# PA_CTRL_TOP.net
KiCad netlist of a schematic drawn in Altium Designer
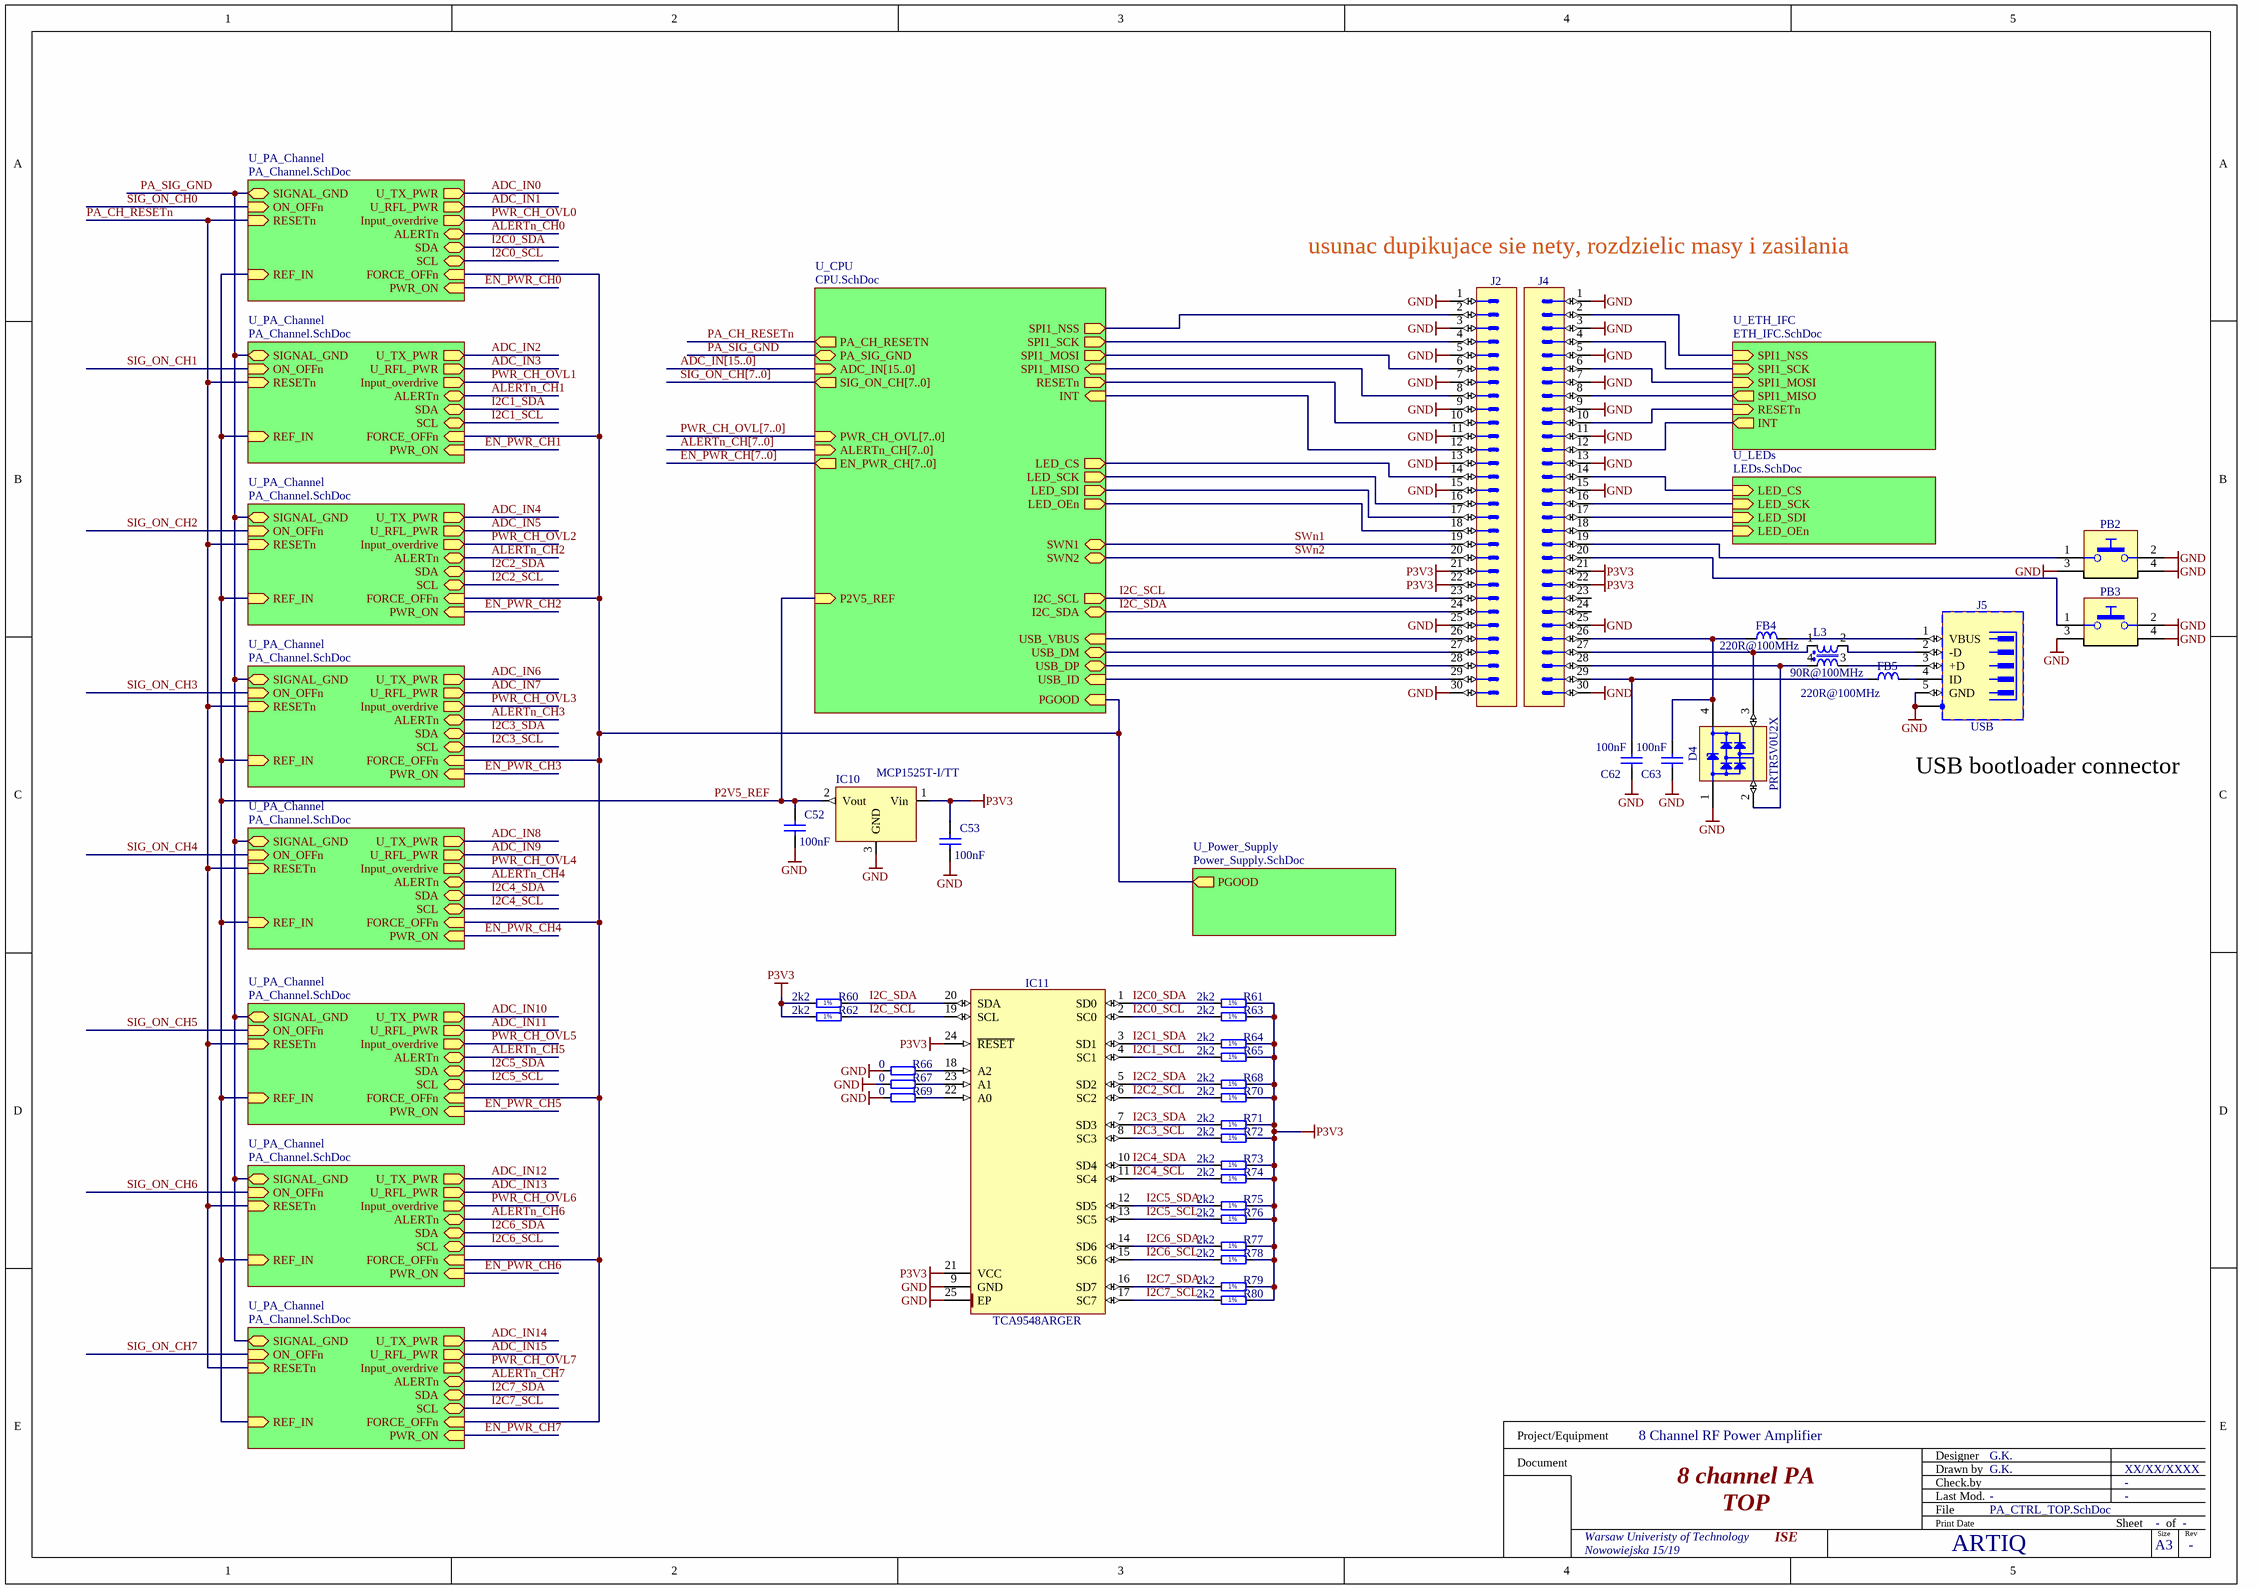
[diagram p0: PA_CTRL_TOP.SchDoc]

(export (version "E")
  (design (tool "Eeschema 10.0.6"))
  (components
    (comp (ref "C52")
      (value "100nF")
      (footprint "CAPC1005X55N")
      (description "Non-polarised capacitor")
      (fields
        (field (name "PART NUMBER") "CC0402_100NF_16V_10%_X7R")
        (field (name "VOLTAGE") "16V")
        (field (name "AUTHOR") "CERN DEM JLC")
      )
      (libsource (lib "Capacitors") (part "Capacitor - non polarized"))
    )
    (comp (ref "C53")
      (value "100nF")
      (footprint "CAPC1005X55N")
      (description "Non-polarised capacitor")
      (fields
        (field (name "PART NUMBER") "CC0402_100NF_16V_10%_X7R")
        (field (name "VOLTAGE") "16V")
        (field (name "AUTHOR") "CERN DEM JLC")
      )
      (libsource (lib "Capacitors") (part "Capacitor - non polarized"))
    )
    (comp (ref "C62")
      (value "100nF")
      (footprint "CAPC0603X33N")
      (description "Non-polarised capacitor")
      (fields
        (field (name "PART NUMBER") "CC0201_100NF_6.3V_10%_X5R")
        (field (name "VOLTAGE") "6.3V")
        (field (name "AUTHOR") "CERN DEM JLC")
      )
      (libsource (lib "Capacitors") (part "Capacitor - non polarized"))
    )
    (comp (ref "C63")
      (value "100nF")
      (footprint "CAPC0603X33N")
      (description "Non-polarised capacitor")
      (fields
        (field (name "PART NUMBER") "CC0201_100NF_6.3V_10%_X5R")
        (field (name "VOLTAGE") "6.3V")
        (field (name "AUTHOR") "CERN DEM JLC")
      )
      (libsource (lib "Capacitors") (part "Capacitor - non polarized"))
    )
    (comp (ref "D4")
      (value "PRTR5V0U2X")
      (footprint "SOT190P230X110-4N")
      (description "Ultra Low Capacitance Double Rail-to-Rail ESD Protection Diode")
      (fields
        (field (name "VOLTAGE") "5.5V")
        (field (name "MANUFACTURER") "NXP SEMICONDUCTORS")
        (field (name "AUTHOR") "CERN DEM JLC")
      )
      (libsource (lib "ICs And Semiconductors") (part "PRTR5V0U2X"))
    )
    (comp (ref "FB4")
      (value "220R@100MHz")
      (footprint "INDC2012X105N")
      (description "Inductor")
      (fields
        (field (name "PART NUMBER") "IND0805_MURATA_BLM21PG221SN1D")
        (field (name "POWER") "2A")
        (field (name "AUTHOR") "CERN DEM JLC")
      )
      (libsource (lib "Inductors & Transformers") (part "Inductor"))
    )
    (comp (ref "FB5")
      (value "220R@100MHz")
      (footprint "INDC2012X105N")
      (description "Inductor")
      (fields
        (field (name "PART NUMBER") "IND0805_MURATA_BLM21PG221SN1D")
        (field (name "POWER") "2A")
        (field (name "AUTHOR") "CERN DEM JLC")
      )
      (libsource (lib "Inductors & Transformers") (part "Inductor"))
    )
    (comp (ref "IC10")
      (value "MCP1525T-I/TT")
      (footprint "SOT95P251X112-3N")
      (description "2.5 voltage reference")
      (libsource (lib "LIBRARY_SCH") (part "REF_MCP1525"))
    )
    (comp (ref "IC11")
      (value "TCA9548ARGER")
      (footprint "QFN50P400X400X100-25N-S220")
      (description "Low Voltage 8-Channel I2C Switch With Reset")
      (fields (field (name "MANUFACTURER") "TEXAS INSTRUMENTS") (field (name "AUTHOR") "CERN DEM JLC"))
      (libsource (lib "ICs And Semiconductors") (part "TCA9548ARGER"))
    )
    (comp (ref "J2")
      (value "~")
      (footprint "3M_N2530-6002RB")
      (description "Connector 30 Male")
      (fields
        (field (name "PART NUMBER") "3M_N2530-6002RB")
        (field (name "MANUFACTURER") "3M")
        (field (name "AUTHOR") "CERN DEM JLC")
      )
      (libsource (lib "Connectors") (part "Connector 30 Male"))
    )
    (comp (ref "J4")
      (value "~")
      (footprint "3M_N2530-6002RB")
      (description "Connector 30 Male")
      (fields
        (field (name "PART NUMBER") "3M_N2530-6002RB")
        (field (name "MANUFACTURER") "3M")
        (field (name "AUTHOR") "CERN DEM JLC")
      )
      (libsource (lib "Connectors") (part "Connector 30 Male"))
    )
    (comp (ref "J5")
      (value "USB")
      (footprint "WURTH_651005136521")
      (description "5 Pin + 1 Shield USB Receptacle")
      (fields
        (field (name "PART NUMBER") "WURTH_651005136521")
        (field (name "MANUFACTURER") "WURTH ELEKTRONIK")
        (field (name "AUTHOR") "CERN DEM JLC")
      )
      (libsource (lib "Connectors") (part "Connector USB 5 Pin + 1Shield"))
    )
    (comp (ref "L3")
      (value "90R@100MHz")
      (footprint "IND_MURATA_DLW21S")
      (description "Inductor Common Mode")
      (fields
        (field (name "PART NUMBER") "IND_MURATA_DLW21SN900SQ2L")
        (field (name "POWER") "330mA")
        (field (name "AUTHOR") "CERN DEM JLC")
      )
      (libsource (lib "Inductors & Transformers") (part "Inductor Common Mode 1Dot-2 4Dot-3"))
    )
    (comp (ref "PB2")
      (value "Push Button")
      (footprint "PB_TYCO_1-1825027-1")
      (description "Push-Button Switch SPDT")
      (fields
        (field (name "PART NUMBER") "PB_TYCO_1-1825027-1")
        (field (name "MANUFACTURER") "TYCO ELECTRONICS")
        (field (name "AUTHOR") "CERN DEM JLC")
      )
      (libsource (lib "Eletro-mechanical") (part "PB SPST 1NO-2NO 34CASE"))
    )
    (comp (ref "PB3")
      (value "Push Button")
      (footprint "PB_TYCO_1-1825027-1")
      (description "Push-Button Switch SPDT")
      (fields
        (field (name "PART NUMBER") "PB_TYCO_1-1825027-1")
        (field (name "MANUFACTURER") "TYCO ELECTRONICS")
        (field (name "AUTHOR") "CERN DEM JLC")
      )
      (libsource (lib "Eletro-mechanical") (part "PB SPST 1NO-2NO 34CASE"))
    )
    (comp (ref "R60")
      (value "2k2")
      (footprint "RESC1005X40N")
      (description "Resistor - 1%")
      (fields
        (field (name "PART NUMBER") "R0402_2K2_1%_0.0625W_100PPM")
        (field (name "POWER") "0.0625W")
        (field (name "AUTHOR") "CERN DEM JLC")
      )
      (libsource (lib "Resistors") (part "Resistor - 1%"))
    )
    (comp (ref "R61")
      (value "2k2")
      (footprint "RESC1005X40N")
      (description "Resistor - 1%")
      (fields
        (field (name "PART NUMBER") "R0402_2K2_1%_0.0625W_100PPM")
        (field (name "POWER") "0.0625W")
        (field (name "AUTHOR") "CERN DEM JLC")
      )
      (libsource (lib "Resistors") (part "Resistor - 1%"))
    )
    (comp (ref "R62")
      (value "2k2")
      (footprint "RESC1005X40N")
      (description "Resistor - 1%")
      (fields
        (field (name "PART NUMBER") "R0402_2K2_1%_0.0625W_100PPM")
        (field (name "POWER") "0.0625W")
        (field (name "AUTHOR") "CERN DEM JLC")
      )
      (libsource (lib "Resistors") (part "Resistor - 1%"))
    )
    (comp (ref "R63")
      (value "2k2")
      (footprint "RESC1005X40N")
      (description "Resistor - 1%")
      (fields
        (field (name "PART NUMBER") "R0402_2K2_1%_0.0625W_100PPM")
        (field (name "POWER") "0.0625W")
        (field (name "AUTHOR") "CERN DEM JLC")
      )
      (libsource (lib "Resistors") (part "Resistor - 1%"))
    )
    (comp (ref "R64")
      (value "2k2")
      (footprint "RESC1005X40N")
      (description "Resistor - 1%")
      (fields
        (field (name "PART NUMBER") "R0402_2K2_1%_0.0625W_100PPM")
        (field (name "POWER") "0.0625W")
        (field (name "AUTHOR") "CERN DEM JLC")
      )
      (libsource (lib "Resistors") (part "Resistor - 1%"))
    )
    (comp (ref "R65")
      (value "2k2")
      (footprint "RESC1005X40N")
      (description "Resistor - 1%")
      (fields
        (field (name "PART NUMBER") "R0402_2K2_1%_0.0625W_100PPM")
        (field (name "POWER") "0.0625W")
        (field (name "AUTHOR") "CERN DEM JLC")
      )
      (libsource (lib "Resistors") (part "Resistor - 1%"))
    )
    (comp (ref "R66")
      (value "0")
      (footprint "RESC1005X40N")
      (description "Resistor")
      (fields
        (field (name "PART NUMBER") "R0402_0R_JUMPER")
        (field (name "MANUFACTURER") "GENERIC")
        (field (name "AUTHOR") "CERN DEM JLC")
      )
      (libsource (lib "Resistors") (part "Resistor"))
    )
    (comp (ref "R67")
      (value "0")
      (footprint "RESC1005X40N")
      (description "Resistor")
      (fields
        (field (name "PART NUMBER") "R0402_0R_JUMPER")
        (field (name "MANUFACTURER") "GENERIC")
        (field (name "AUTHOR") "CERN DEM JLC")
      )
      (libsource (lib "Resistors") (part "Resistor"))
    )
    (comp (ref "R68")
      (value "2k2")
      (footprint "RESC1005X40N")
      (description "Resistor - 1%")
      (fields
        (field (name "PART NUMBER") "R0402_2K2_1%_0.0625W_100PPM")
        (field (name "POWER") "0.0625W")
        (field (name "AUTHOR") "CERN DEM JLC")
      )
      (libsource (lib "Resistors") (part "Resistor - 1%"))
    )
    (comp (ref "R69")
      (value "0")
      (footprint "RESC1005X40N")
      (description "Resistor")
      (fields
        (field (name "PART NUMBER") "R0402_0R_JUMPER")
        (field (name "MANUFACTURER") "GENERIC")
        (field (name "AUTHOR") "CERN DEM JLC")
      )
      (libsource (lib "Resistors") (part "Resistor"))
    )
    (comp (ref "R70")
      (value "2k2")
      (footprint "RESC1005X40N")
      (description "Resistor - 1%")
      (fields
        (field (name "PART NUMBER") "R0402_2K2_1%_0.0625W_100PPM")
        (field (name "POWER") "0.0625W")
        (field (name "AUTHOR") "CERN DEM JLC")
      )
      (libsource (lib "Resistors") (part "Resistor - 1%"))
    )
    (comp (ref "R71")
      (value "2k2")
      (footprint "RESC1005X40N")
      (description "Resistor - 1%")
      (fields
        (field (name "PART NUMBER") "R0402_2K2_1%_0.0625W_100PPM")
        (field (name "POWER") "0.0625W")
        (field (name "AUTHOR") "CERN DEM JLC")
      )
      (libsource (lib "Resistors") (part "Resistor - 1%"))
    )
    (comp (ref "R72")
      (value "2k2")
      (footprint "RESC1005X40N")
      (description "Resistor - 1%")
      (fields
        (field (name "PART NUMBER") "R0402_2K2_1%_0.0625W_100PPM")
        (field (name "POWER") "0.0625W")
        (field (name "AUTHOR") "CERN DEM JLC")
      )
      (libsource (lib "Resistors") (part "Resistor - 1%"))
    )
    (comp (ref "R73")
      (value "2k2")
      (footprint "RESC1005X40N")
      (description "Resistor - 1%")
      (fields
        (field (name "PART NUMBER") "R0402_2K2_1%_0.0625W_100PPM")
        (field (name "POWER") "0.0625W")
        (field (name "AUTHOR") "CERN DEM JLC")
      )
      (libsource (lib "Resistors") (part "Resistor - 1%"))
    )
    (comp (ref "R74")
      (value "2k2")
      (footprint "RESC1005X40N")
      (description "Resistor - 1%")
      (fields
        (field (name "PART NUMBER") "R0402_2K2_1%_0.0625W_100PPM")
        (field (name "POWER") "0.0625W")
        (field (name "AUTHOR") "CERN DEM JLC")
      )
      (libsource (lib "Resistors") (part "Resistor - 1%"))
    )
    (comp (ref "R75")
      (value "2k2")
      (footprint "RESC1005X40N")
      (description "Resistor - 1%")
      (fields
        (field (name "PART NUMBER") "R0402_2K2_1%_0.0625W_100PPM")
        (field (name "POWER") "0.0625W")
        (field (name "AUTHOR") "CERN DEM JLC")
      )
      (libsource (lib "Resistors") (part "Resistor - 1%"))
    )
    (comp (ref "R76")
      (value "2k2")
      (footprint "RESC1005X40N")
      (description "Resistor - 1%")
      (fields
        (field (name "PART NUMBER") "R0402_2K2_1%_0.0625W_100PPM")
        (field (name "POWER") "0.0625W")
        (field (name "AUTHOR") "CERN DEM JLC")
      )
      (libsource (lib "Resistors") (part "Resistor - 1%"))
    )
    (comp (ref "R77")
      (value "2k2")
      (footprint "RESC1005X40N")
      (description "Resistor - 1%")
      (fields
        (field (name "PART NUMBER") "R0402_2K2_1%_0.0625W_100PPM")
        (field (name "POWER") "0.0625W")
        (field (name "AUTHOR") "CERN DEM JLC")
      )
      (libsource (lib "Resistors") (part "Resistor - 1%"))
    )
    (comp (ref "R78")
      (value "2k2")
      (footprint "RESC1005X40N")
      (description "Resistor - 1%")
      (fields
        (field (name "PART NUMBER") "R0402_2K2_1%_0.0625W_100PPM")
        (field (name "POWER") "0.0625W")
        (field (name "AUTHOR") "CERN DEM JLC")
      )
      (libsource (lib "Resistors") (part "Resistor - 1%"))
    )
    (comp (ref "R79")
      (value "2k2")
      (footprint "RESC1005X40N")
      (description "Resistor - 1%")
      (fields
        (field (name "PART NUMBER") "R0402_2K2_1%_0.0625W_100PPM")
        (field (name "POWER") "0.0625W")
        (field (name "AUTHOR") "CERN DEM JLC")
      )
      (libsource (lib "Resistors") (part "Resistor - 1%"))
    )
    (comp (ref "R80")
      (value "2k2")
      (footprint "RESC1005X40N")
      (description "Resistor - 1%")
      (fields
        (field (name "PART NUMBER") "R0402_2K2_1%_0.0625W_100PPM")
        (field (name "POWER") "0.0625W")
        (field (name "AUTHOR") "CERN DEM JLC")
      )
      (libsource (lib "Resistors") (part "Resistor - 1%"))
    )
  )
  (nets
    (net (code "36") (name "/I2C0_SCL") (class "Default")
      (node (ref "IC11") (pin "2") (pinfunction "SC0_2") (pintype "bidirectional"))
      (node (ref "R63") (pin "1") (pinfunction "1_1") (pintype "passive"))
    )
    (net (code "37") (name "/I2C0_SDA") (class "Default")
      (node (ref "IC11") (pin "1") (pinfunction "SD0_1") (pintype "bidirectional"))
      (node (ref "R61") (pin "1") (pinfunction "1_1") (pintype "passive"))
    )
    (net (code "38") (name "/I2C1_SCL") (class "Default")
      (node (ref "IC11") (pin "4") (pinfunction "SC1_4") (pintype "bidirectional"))
      (node (ref "R65") (pin "1") (pinfunction "1_1") (pintype "passive"))
    )
    (net (code "39") (name "/I2C1_SDA") (class "Default")
      (node (ref "IC11") (pin "3") (pinfunction "SD1_3") (pintype "bidirectional"))
      (node (ref "R64") (pin "1") (pinfunction "1_1") (pintype "passive"))
    )
    (net (code "40") (name "/I2C2_SCL") (class "Default")
      (node (ref "IC11") (pin "6") (pinfunction "SC2_6") (pintype "bidirectional"))
      (node (ref "R70") (pin "1") (pinfunction "1_1") (pintype "passive"))
    )
    (net (code "41") (name "/I2C2_SDA") (class "Default")
      (node (ref "IC11") (pin "5") (pinfunction "SD2_5") (pintype "bidirectional"))
      (node (ref "R68") (pin "1") (pinfunction "1_1") (pintype "passive"))
    )
    (net (code "42") (name "/I2C3_SCL") (class "Default")
      (node (ref "IC11") (pin "8") (pinfunction "SC3_8") (pintype "bidirectional"))
      (node (ref "R72") (pin "1") (pinfunction "1_1") (pintype "passive"))
    )
    (net (code "43") (name "/I2C3_SDA") (class "Default")
      (node (ref "IC11") (pin "7") (pinfunction "SD3_7") (pintype "bidirectional"))
      (node (ref "R71") (pin "1") (pinfunction "1_1") (pintype "passive"))
    )
    (net (code "44") (name "/I2C4_SCL") (class "Default")
      (node (ref "IC11") (pin "11") (pinfunction "SC4_11") (pintype "bidirectional"))
      (node (ref "R74") (pin "1") (pinfunction "1_1") (pintype "passive"))
    )
    (net (code "45") (name "/I2C4_SDA") (class "Default")
      (node (ref "IC11") (pin "10") (pinfunction "SD4_10") (pintype "bidirectional"))
      (node (ref "R73") (pin "1") (pinfunction "1_1") (pintype "passive"))
    )
    (net (code "46") (name "/I2C5_SCL") (class "Default")
      (node (ref "IC11") (pin "13") (pinfunction "SC5_13") (pintype "bidirectional"))
      (node (ref "R76") (pin "1") (pinfunction "1_1") (pintype "passive"))
    )
    (net (code "47") (name "/I2C5_SDA") (class "Default")
      (node (ref "IC11") (pin "12") (pinfunction "SD5_12") (pintype "bidirectional"))
      (node (ref "R75") (pin "1") (pinfunction "1_1") (pintype "passive"))
    )
    (net (code "48") (name "/I2C6_SCL") (class "Default")
      (node (ref "IC11") (pin "15") (pinfunction "SC6_15") (pintype "bidirectional"))
      (node (ref "R78") (pin "1") (pinfunction "1_1") (pintype "passive"))
    )
    (net (code "49") (name "/I2C6_SDA") (class "Default")
      (node (ref "IC11") (pin "14") (pinfunction "SD6_14") (pintype "bidirectional"))
      (node (ref "R77") (pin "1") (pinfunction "1_1") (pintype "passive"))
    )
    (net (code "50") (name "/I2C7_SCL") (class "Default")
      (node (ref "IC11") (pin "17") (pinfunction "SC7_17") (pintype "bidirectional"))
      (node (ref "R80") (pin "1") (pinfunction "1_1") (pintype "passive"))
    )
    (net (code "51") (name "/I2C7_SDA") (class "Default")
      (node (ref "IC11") (pin "16") (pinfunction "SD7_16") (pintype "bidirectional"))
      (node (ref "R79") (pin "1") (pinfunction "1_1") (pintype "passive"))
    )
    (net (code "52") (name "/I2C_SCL") (class "Default")
      (node (ref "IC11") (pin "19") (pinfunction "SCL_19") (pintype "bidirectional"))
      (node (ref "J2") (pin "23") (pinfunction "23_23") (pintype "bidirectional"))
      (node (ref "R62") (pin "2") (pinfunction "2_2") (pintype "passive"))
    )
    (net (code "53") (name "/I2C_SDA") (class "Default")
      (node (ref "IC11") (pin "20") (pinfunction "SDA_20") (pintype "bidirectional"))
      (node (ref "J2") (pin "24") (pinfunction "24_24") (pintype "bidirectional"))
      (node (ref "R60") (pin "2") (pinfunction "2_2") (pintype "passive"))
    )
    (net (code "54") (name "/INT") (class "Default")
      (node (ref "J4") (pin "12") (pinfunction "12_12") (pintype "bidirectional"))
    )
    (net (code "55") (name "/INT_1") (class "Default")
      (node (ref "J2") (pin "12") (pinfunction "12_12") (pintype "bidirectional"))
    )
    (net (code "56") (name "/LED_CS") (class "Default")
      (node (ref "J4") (pin "14") (pinfunction "14_14") (pintype "bidirectional"))
    )
    (net (code "57") (name "/LED_CS_1") (class "Default")
      (node (ref "J2") (pin "14") (pinfunction "14_14") (pintype "bidirectional"))
    )
    (net (code "58") (name "/LED_OEn") (class "Default")
      (node (ref "J2") (pin "18") (pinfunction "18_18") (pintype "bidirectional"))
    )
    (net (code "59") (name "/LED_OEn_1") (class "Default")
      (node (ref "J4") (pin "18") (pinfunction "18_18") (pintype "bidirectional"))
    )
    (net (code "60") (name "/LED_SCK") (class "Default")
      (node (ref "J2") (pin "16") (pinfunction "16_16") (pintype "bidirectional"))
    )
    (net (code "61") (name "/LED_SCK_1") (class "Default")
      (node (ref "J4") (pin "16") (pinfunction "16_16") (pintype "bidirectional"))
    )
    (net (code "62") (name "/LED_SDI") (class "Default")
      (node (ref "J2") (pin "17") (pinfunction "17_17") (pintype "bidirectional"))
    )
    (net (code "63") (name "/LED_SDI_1") (class "Default")
      (node (ref "J4") (pin "17") (pinfunction "17_17") (pintype "bidirectional"))
    )
    (net (code "64") (name "/P2V5_REF") (class "Default")
      (node (ref "C52") (pin "1") (pinfunction "1_1") (pintype "passive"))
      (node (ref "IC10") (pin "2") (pinfunction "Vout_2") (pintype "output"))
    )
    (net (code "77") (name "/RESETn") (class "Default")
      (node (ref "J4") (pin "10") (pinfunction "10_10") (pintype "bidirectional"))
    )
    (net (code "78") (name "/RESETn_1") (class "Default")
      (node (ref "J2") (pin "10") (pinfunction "10_10") (pintype "bidirectional"))
    )
    (net (code "88") (name "/SPI1_MISO") (class "Default")
      (node (ref "J4") (pin "8") (pinfunction "8_8") (pintype "bidirectional"))
    )
    (net (code "89") (name "/SPI1_MISO_1") (class "Default")
      (node (ref "J2") (pin "8") (pinfunction "8_8") (pintype "bidirectional"))
    )
    (net (code "90") (name "/SPI1_MOSI") (class "Default")
      (node (ref "J4") (pin "6") (pinfunction "6_6") (pintype "bidirectional"))
    )
    (net (code "91") (name "/SPI1_MOSI_1") (class "Default")
      (node (ref "J2") (pin "6") (pinfunction "6_6") (pintype "bidirectional"))
    )
    (net (code "92") (name "/SPI1_NSS") (class "Default")
      (node (ref "J2") (pin "2") (pinfunction "2_2") (pintype "bidirectional"))
    )
    (net (code "93") (name "/SPI1_NSS_1") (class "Default")
      (node (ref "J4") (pin "2") (pinfunction "2_2") (pintype "bidirectional"))
    )
    (net (code "94") (name "/SPI1_SCK") (class "Default")
      (node (ref "J2") (pin "4") (pinfunction "4_4") (pintype "bidirectional"))
    )
    (net (code "95") (name "/SPI1_SCK_1") (class "Default")
      (node (ref "J4") (pin "4") (pinfunction "4_4") (pintype "bidirectional"))
    )
    (net (code "96") (name "/SWn1") (class "Default")
      (node (ref "J2") (pin "19") (pinfunction "19_19") (pintype "bidirectional"))
    )
    (net (code "97") (name "/SWn2") (class "Default")
      (node (ref "J2") (pin "20") (pinfunction "20_20") (pintype "bidirectional"))
    )
    (net (code "98") (name "/USB_DM") (class "Default")
      (node (ref "J2") (pin "27") (pinfunction "27_27") (pintype "bidirectional"))
    )
    (net (code "99") (name "/USB_DP") (class "Default")
      (node (ref "J2") (pin "28") (pinfunction "28_28") (pintype "bidirectional"))
    )
    (net (code "100") (name "/USB_ID") (class "Default")
      (node (ref "J2") (pin "29") (pinfunction "29_29") (pintype "bidirectional"))
    )
    (net (code "101") (name "/USB_VBUS") (class "Default")
      (node (ref "J2") (pin "26") (pinfunction "26_26") (pintype "bidirectional"))
    )
    (net (code "102") (name "GND") (class "Default")
      (node (ref "C52") (pin "2") (pinfunction "2_2") (pintype "passive"))
      (node (ref "C53") (pin "2") (pinfunction "2_2") (pintype "passive"))
      (node (ref "C62") (pin "1") (pinfunction "1_1") (pintype "passive"))
      (node (ref "C63") (pin "1") (pinfunction "1_1") (pintype "passive"))
      (node (ref "D4") (pin "1") (pinfunction "GND_1") (pintype "power_in"))
      (node (ref "IC10") (pin "3") (pinfunction "GND_3") (pintype "power_in"))
      (node (ref "IC11") (pin "25") (pinfunction "EP_25") (pintype "power_in"))
      (node (ref "IC11") (pin "9") (pinfunction "GND_9") (pintype "power_in"))
      (node (ref "J2") (pin "1") (pinfunction "1_1") (pintype "bidirectional"))
      (node (ref "J2") (pin "11") (pinfunction "11_11") (pintype "bidirectional"))
      (node (ref "J2") (pin "13") (pinfunction "13_13") (pintype "bidirectional"))
      (node (ref "J2") (pin "15") (pinfunction "15_15") (pintype "bidirectional"))
      (node (ref "J2") (pin "25") (pinfunction "25_25") (pintype "bidirectional"))
      (node (ref "J2") (pin "3") (pinfunction "3_3") (pintype "bidirectional"))
      (node (ref "J2") (pin "30") (pinfunction "30_30") (pintype "bidirectional"))
      (node (ref "J2") (pin "5") (pinfunction "5_5") (pintype "bidirectional"))
      (node (ref "J2") (pin "7") (pinfunction "7_7") (pintype "bidirectional"))
      (node (ref "J2") (pin "9") (pinfunction "9_9") (pintype "bidirectional"))
      (node (ref "J4") (pin "1") (pinfunction "1_1") (pintype "bidirectional"))
      (node (ref "J4") (pin "11") (pinfunction "11_11") (pintype "bidirectional"))
      (node (ref "J4") (pin "13") (pinfunction "13_13") (pintype "bidirectional"))
      (node (ref "J4") (pin "15") (pinfunction "15_15") (pintype "bidirectional"))
      (node (ref "J4") (pin "25") (pinfunction "25_25") (pintype "bidirectional"))
      (node (ref "J4") (pin "3") (pinfunction "3_3") (pintype "bidirectional"))
      (node (ref "J4") (pin "30") (pinfunction "30_30") (pintype "bidirectional"))
      (node (ref "J4") (pin "5") (pinfunction "5_5") (pintype "bidirectional"))
      (node (ref "J4") (pin "7") (pinfunction "7_7") (pintype "bidirectional"))
      (node (ref "J4") (pin "9") (pinfunction "9_9") (pintype "bidirectional"))
      (node (ref "J5") (pin "5") (pinfunction "GND_5") (pintype "bidirectional"))
      (node (ref "J5") (pin "6") (pinfunction "SH_6") (pintype "power_in"))
      (node (ref "PB2") (pin "2") (pinfunction "2_2") (pintype "passive"))
      (node (ref "PB2") (pin "3") (pinfunction "3_3") (pintype "passive"))
      (node (ref "PB2") (pin "4") (pinfunction "4_4") (pintype "passive"))
      (node (ref "PB3") (pin "2") (pinfunction "2_2") (pintype "passive"))
      (node (ref "PB3") (pin "3") (pinfunction "3_3") (pintype "passive"))
      (node (ref "PB3") (pin "4") (pinfunction "4_4") (pintype "passive"))
      (node (ref "R66") (pin "1") (pinfunction "1_1") (pintype "passive"))
      (node (ref "R67") (pin "1") (pinfunction "1_1") (pintype "passive"))
      (node (ref "R69") (pin "1") (pinfunction "1_1") (pintype "passive"))
    )
    (net (code "103") (name "Net-(C62-Pad2)") (class "Default")
      (node (ref "C62") (pin "2") (pinfunction "2_2") (pintype "passive"))
      (node (ref "FB5") (pin "1") (pinfunction "1_1") (pintype "passive"))
      (node (ref "J4") (pin "29") (pinfunction "29_29") (pintype "bidirectional"))
    )
    (net (code "104") (name "Net-(D4-I{slash}O1)") (class "Default")
      (node (ref "D4") (pin "2") (pinfunction "I/O1_2") (pintype "bidirectional"))
      (node (ref "J4") (pin "28") (pinfunction "28_28") (pintype "bidirectional"))
      (node (ref "L3") (pin "4") (pinfunction "4_4") (pintype "passive"))
    )
    (net (code "105") (name "Net-(D4-I{slash}O2)") (class "Default")
      (node (ref "D4") (pin "3") (pinfunction "I/O2_3") (pintype "bidirectional"))
      (node (ref "J4") (pin "27") (pinfunction "27_27") (pintype "bidirectional"))
      (node (ref "L3") (pin "1") (pinfunction "1_1") (pintype "passive"))
    )
    (net (code "106") (name "Net-(D4-VCC)") (class "Default")
      (node (ref "C63") (pin "2") (pinfunction "2_2") (pintype "passive"))
      (node (ref "D4") (pin "4") (pinfunction "VCC_4") (pintype "power_in"))
      (node (ref "FB4") (pin "1") (pinfunction "1_1") (pintype "passive"))
      (node (ref "J4") (pin "26") (pinfunction "26_26") (pintype "bidirectional"))
    )
    (net (code "107") (name "Net-(IC11-A0)") (class "Default")
      (node (ref "IC11") (pin "22") (pinfunction "A0_22") (pintype "input"))
      (node (ref "R69") (pin "2") (pinfunction "2_2") (pintype "passive"))
    )
    (net (code "108") (name "Net-(IC11-A1)") (class "Default")
      (node (ref "IC11") (pin "23") (pinfunction "A1_23") (pintype "input"))
      (node (ref "R67") (pin "2") (pinfunction "2_2") (pintype "passive"))
    )
    (net (code "109") (name "Net-(IC11-A2)") (class "Default")
      (node (ref "IC11") (pin "18") (pinfunction "A2_18") (pintype "input"))
      (node (ref "R66") (pin "2") (pinfunction "2_2") (pintype "passive"))
    )
    (net (code "110") (name "Net-(J4-Pad19)") (class "Default")
      (node (ref "J4") (pin "19") (pinfunction "19_19") (pintype "bidirectional"))
      (node (ref "PB2") (pin "1") (pinfunction "1_1") (pintype "passive"))
    )
    (net (code "111") (name "Net-(J4-Pad20)") (class "Default")
      (node (ref "J4") (pin "20") (pinfunction "20_20") (pintype "bidirectional"))
      (node (ref "PB3") (pin "1") (pinfunction "1_1") (pintype "passive"))
    )
    (net (code "112") (name "Net-(J5-+D)") (class "Default")
      (node (ref "J5") (pin "3") (pinfunction "+D_3") (pintype "bidirectional"))
      (node (ref "L3") (pin "3") (pinfunction "3_3") (pintype "passive"))
    )
    (net (code "113") (name "Net-(J5--D)") (class "Default")
      (node (ref "J5") (pin "2") (pinfunction "-D_2") (pintype "bidirectional"))
      (node (ref "L3") (pin "2") (pinfunction "2_2") (pintype "passive"))
    )
    (net (code "114") (name "Net-(J5-ID)") (class "Default")
      (node (ref "FB5") (pin "2") (pinfunction "2_2") (pintype "passive"))
      (node (ref "J5") (pin "4") (pinfunction "ID_4") (pintype "passive"))
    )
    (net (code "115") (name "Net-(J5-VBUS)") (class "Default")
      (node (ref "FB4") (pin "2") (pinfunction "2_2") (pintype "passive"))
      (node (ref "J5") (pin "1") (pinfunction "VBUS_1") (pintype "bidirectional"))
    )
    (net (code "116") (name "P3V3") (class "Default")
      (node (ref "C53") (pin "1") (pinfunction "1_1") (pintype "passive"))
      (node (ref "IC10") (pin "1") (pinfunction "Vin_1") (pintype "power_in"))
      (node (ref "IC11") (pin "21") (pinfunction "VCC_21") (pintype "power_in"))
      (node (ref "IC11") (pin "24") (pinfunction "~{RESET}_24") (pintype "input"))
      (node (ref "J2") (pin "21") (pinfunction "21_21") (pintype "bidirectional"))
      (node (ref "J2") (pin "22") (pinfunction "22_22") (pintype "bidirectional"))
      (node (ref "J4") (pin "21") (pinfunction "21_21") (pintype "bidirectional"))
      (node (ref "J4") (pin "22") (pinfunction "22_22") (pintype "bidirectional"))
      (node (ref "R60") (pin "1") (pinfunction "1_1") (pintype "passive"))
      (node (ref "R61") (pin "2") (pinfunction "2_2") (pintype "passive"))
      (node (ref "R62") (pin "1") (pinfunction "1_1") (pintype "passive"))
      (node (ref "R63") (pin "2") (pinfunction "2_2") (pintype "passive"))
      (node (ref "R64") (pin "2") (pinfunction "2_2") (pintype "passive"))
      (node (ref "R65") (pin "2") (pinfunction "2_2") (pintype "passive"))
      (node (ref "R68") (pin "2") (pinfunction "2_2") (pintype "passive"))
      (node (ref "R70") (pin "2") (pinfunction "2_2") (pintype "passive"))
      (node (ref "R71") (pin "2") (pinfunction "2_2") (pintype "passive"))
      (node (ref "R72") (pin "2") (pinfunction "2_2") (pintype "passive"))
      (node (ref "R73") (pin "2") (pinfunction "2_2") (pintype "passive"))
      (node (ref "R74") (pin "2") (pinfunction "2_2") (pintype "passive"))
      (node (ref "R75") (pin "2") (pinfunction "2_2") (pintype "passive"))
      (node (ref "R76") (pin "2") (pinfunction "2_2") (pintype "passive"))
      (node (ref "R77") (pin "2") (pinfunction "2_2") (pintype "passive"))
      (node (ref "R78") (pin "2") (pinfunction "2_2") (pintype "passive"))
      (node (ref "R79") (pin "2") (pinfunction "2_2") (pintype "passive"))
      (node (ref "R80") (pin "2") (pinfunction "2_2") (pintype "passive"))
    )
    (net (code "117") (name "unconnected-(J4-Pad23)") (class "Default")
      (node (ref "J4") (pin "23") (pinfunction "23_23") (pintype "bidirectional"))
    )
    (net (code "118") (name "unconnected-(J4-Pad24)") (class "Default")
      (node (ref "J4") (pin "24") (pinfunction "24_24") (pintype "bidirectional"))
    )
  )
)
